# ESP32-C6_Qwiic_Micro.net
KiCad netlist of a schematic drawn in EAGLE
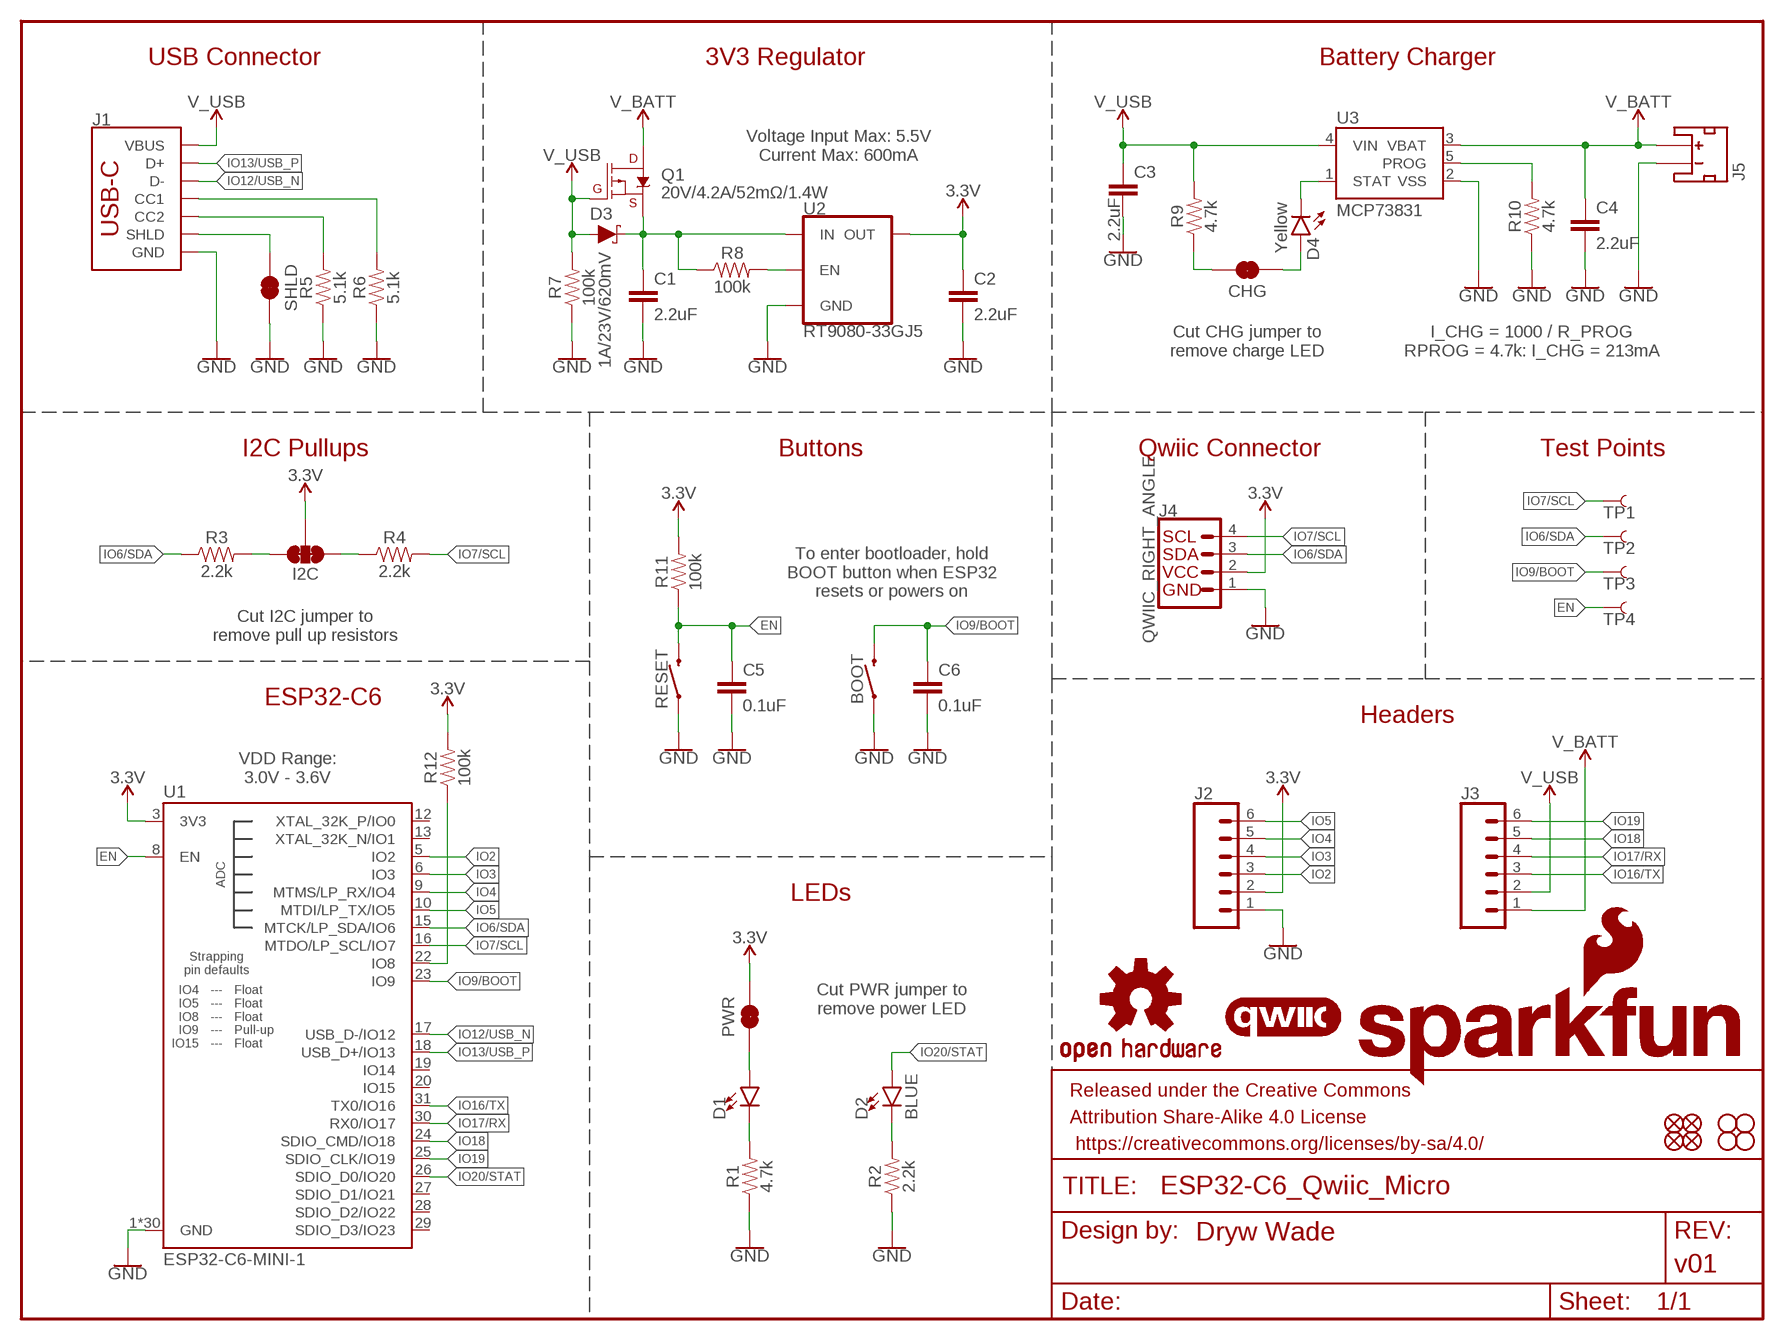
[diagram p0: schematic, sheet 1]

(export (version "E")
  (design (tool "Eeschema 10.0.6"))
  (components
    (comp (ref "BOOT")
      (value "MOMENTARY-SWITCH-SPST-SMD-4.6X2.8MM")
      (footprint "eagle-import:TACTILE_SWITCH_SMD_4.6X2.8MM")
      (libsource (lib "eagle-import") (part "MOMENTARY-SWITCH-SPST-SMD-4.6X2.8MM"))
    )
    (comp (ref "C1")
      (value "2.2uF")
      (footprint "eagle-import:0402-TIGHT")
      (libsource (lib "eagle-import") (part "2.2UF-0402_TIGHT-10V-10%-X5R"))
    )
    (comp (ref "C2")
      (value "2.2uF")
      (footprint "eagle-import:0402-TIGHT")
      (libsource (lib "eagle-import") (part "2.2UF-0402_TIGHT-10V-10%-X5R"))
    )
    (comp (ref "C3")
      (value "2.2uF")
      (footprint "eagle-import:0402-TIGHT")
      (libsource (lib "eagle-import") (part "2.2UF-0402_TIGHT-10V-10%-X5R"))
    )
    (comp (ref "C4")
      (value "2.2uF")
      (footprint "eagle-import:0402-TIGHT")
      (libsource (lib "eagle-import") (part "2.2UF-0402_TIGHT-10V-10%-X5R"))
    )
    (comp (ref "C5")
      (value "0.1uF")
      (footprint "eagle-import:0402-TIGHT")
      (libsource (lib "eagle-import") (part "0.1UF-0402T-6.3V-10%-X7R"))
    )
    (comp (ref "C6")
      (value "0.1uF")
      (footprint "eagle-import:0402-TIGHT")
      (libsource (lib "eagle-import") (part "0.1UF-0402T-6.3V-10%-X7R"))
    )
    (comp (ref "CHG")
      (value "JUMPER-SMT_2_NC_TRACE_SILK")
      (footprint "eagle-import:SMT-JUMPER_2_NC_TRACE_SILK")
      (libsource (lib "eagle-import") (part "JUMPER-SMT_2_NC_TRACE_SILK"))
    )
    (comp (ref "D1")
      (value "LED-RED_0603-KB")
      (footprint "eagle-import:LED-0603")
      (libsource (lib "eagle-import") (part "LED-RED_0603-KB"))
    )
    (comp (ref "D2")
      (value "BLUE")
      (footprint "eagle-import:LED-0603")
      (libsource (lib "eagle-import") (part "LED-BLUE0603"))
    )
    (comp (ref "D3")
      (value "1A/23V/620mV")
      (footprint "eagle-import:SOD-323")
      (libsource (lib "eagle-import") (part "DIODE-SCHOTTKY-BAT20J"))
    )
    (comp (ref "D4")
      (value "Yellow")
      (footprint "eagle-import:LED-0603")
      (libsource (lib "eagle-import") (part "LED-YELLOW0603"))
    )
    (comp (ref "FD1")
      (value "FIDUCIALUFIDUCIAL")
      (footprint "eagle-import:FIDUCIAL-MICRO")
      (libsource (lib "eagle-import") (part "FIDUCIALUFIDUCIAL"))
    )
    (comp (ref "FD2")
      (value "FIDUCIALUFIDUCIAL")
      (footprint "eagle-import:FIDUCIAL-MICRO")
      (libsource (lib "eagle-import") (part "FIDUCIALUFIDUCIAL"))
    )
    (comp (ref "FD3")
      (value "FIDUCIALUFIDUCIAL")
      (footprint "eagle-import:FIDUCIAL-MICRO")
      (libsource (lib "eagle-import") (part "FIDUCIALUFIDUCIAL"))
    )
    (comp (ref "FD4")
      (value "FIDUCIALUFIDUCIAL")
      (footprint "eagle-import:FIDUCIAL-MICRO")
      (libsource (lib "eagle-import") (part "FIDUCIALUFIDUCIAL"))
    )
    (comp (ref "FRAME1")
      (value "FRAME-LETTER")
      (footprint "eagle-import:CREATIVE_COMMONS")
      (fields (field (name "DESIGNER") "Dryw Wade") (field (name "REV") "v01"))
      (libsource (lib "eagle-import") (part "FRAME-LETTER"))
    )
    (comp (ref "H1")
      (value "STAND-OFF")
      (footprint "eagle-import:STAND-OFF")
      (libsource (lib "eagle-import") (part "STAND-OFF"))
    )
    (comp (ref "H2")
      (value "STAND-OFF")
      (footprint "eagle-import:STAND-OFF")
      (libsource (lib "eagle-import") (part "STAND-OFF"))
    )
    (comp (ref "H3")
      (value "STAND-OFF")
      (footprint "eagle-import:STAND-OFF")
      (libsource (lib "eagle-import") (part "STAND-OFF"))
    )
    (comp (ref "H4")
      (value "STAND-OFF")
      (footprint "eagle-import:STAND-OFF")
      (libsource (lib "eagle-import") (part "STAND-OFF"))
    )
    (comp (ref "I2C")
      (value "JUMPER-SMT_3_2-NC_TRACE_SILK")
      (footprint "eagle-import:SMT-JUMPER_3_2-NC_TRACE_SILK")
      (libsource (lib "eagle-import") (part "JUMPER-SMT_3_2-NC_TRACE_SILK"))
    )
    (comp (ref "J1")
      (value "USB Female Type C Connector")
      (footprint "eagle-import:USB-C-16P_4LAYER-PADS")
      (libsource (lib "eagle-import") (part "USB_C_4-LAYER_PADS"))
    )
    (comp (ref "J2")
      (value "CONN_06NO_SILK_NO_POP")
      (footprint "eagle-import:1X06_NO_SILK")
      (libsource (lib "eagle-import") (part "CONN_06NO_SILK_NO_POP"))
    )
    (comp (ref "J3")
      (value "CONN_06NO_SILK_NO_POP")
      (footprint "eagle-import:1X06_NO_SILK")
      (libsource (lib "eagle-import") (part "CONN_06NO_SILK_NO_POP"))
    )
    (comp (ref "J4")
      (value "QWIIC_RIGHT_ANGLE")
      (footprint "eagle-import:JST04_1MM_RA")
      (libsource (lib "eagle-import") (part "QWIIC_CONNECTORJS-1MM"))
    )
    (comp (ref "J5")
      (value "JST_2MM_MALE")
      (footprint "eagle-import:JST-2-SMD")
      (libsource (lib "eagle-import") (part "JST_2MM_MALE"))
    )
    (comp (ref "LOGO1")
      (value "SFE_LOGO_NAME_FLAMEBLANK")
      (footprint "eagle-import:BLANK")
      (libsource (lib "eagle-import") (part "SFE_LOGO_NAME_FLAMEBLANK"))
    )
    (comp (ref "LOGO2")
      (value "OSHW-LOGOS")
      (footprint "eagle-import:OSHW-LOGO-S")
      (libsource (lib "eagle-import") (part "OSHW-LOGOS"))
    )
    (comp (ref "LOGO3")
      (value "QWIIC_LOGO_3MM")
      (footprint "eagle-import:QWIIC_3MM")
      (libsource (lib "eagle-import") (part "QWIIC_LOGO_3MM"))
    )
    (comp (ref "PWR")
      (value "JUMPER-SMT_2_NC_TRACE_SILK")
      (footprint "eagle-import:SMT-JUMPER_2_NC_TRACE_SILK")
      (libsource (lib "eagle-import") (part "JUMPER-SMT_2_NC_TRACE_SILK"))
    )
    (comp (ref "Q1")
      (value "20V/4.2A/52mΩ/1.4W")
      (footprint "eagle-import:SOT23-3")
      (libsource (lib "eagle-import") (part "MOSFET_PCH-DMG2305UX-7"))
    )
    (comp (ref "R1")
      (value "4.7k")
      (footprint "eagle-import:0402-TIGHT")
      (libsource (lib "eagle-import") (part "4.7KOHM-0402T-1/16W-1%"))
    )
    (comp (ref "R2")
      (value "2.2k")
      (footprint "eagle-import:0402-TIGHT")
      (libsource (lib "eagle-import") (part "2.2KOHM-0402T-1/16W-1%"))
    )
    (comp (ref "R3")
      (value "2.2k")
      (footprint "eagle-import:0402-TIGHT")
      (libsource (lib "eagle-import") (part "2.2KOHM-0402T-1/16W-1%"))
    )
    (comp (ref "R4")
      (value "2.2k")
      (footprint "eagle-import:0402-TIGHT")
      (libsource (lib "eagle-import") (part "2.2KOHM-0402T-1/16W-1%"))
    )
    (comp (ref "R5")
      (value "5.1k")
      (footprint "eagle-import:0402-TIGHT")
      (libsource (lib "eagle-import") (part "5.1KOHM-0402T-1/16W-1%"))
    )
    (comp (ref "R6")
      (value "5.1k")
      (footprint "eagle-import:0402-TIGHT")
      (libsource (lib "eagle-import") (part "5.1KOHM-0402T-1/16W-1%"))
    )
    (comp (ref "R7")
      (value "100k")
      (footprint "eagle-import:0402-TIGHT")
      (libsource (lib "eagle-import") (part "100KOHM-0402T-1/16W-1%"))
    )
    (comp (ref "R8")
      (value "100k")
      (footprint "eagle-import:0402-TIGHT")
      (libsource (lib "eagle-import") (part "100KOHM-0402T-1/16W-1%"))
    )
    (comp (ref "R9")
      (value "4.7k")
      (footprint "eagle-import:0402-TIGHT")
      (libsource (lib "eagle-import") (part "4.7KOHM-0402T-1/16W-1%"))
    )
    (comp (ref "R10")
      (value "4.7k")
      (footprint "eagle-import:0402-TIGHT")
      (libsource (lib "eagle-import") (part "4.7KOHM-0402T-1/16W-1%"))
    )
    (comp (ref "R11")
      (value "100k")
      (footprint "eagle-import:0402-TIGHT")
      (libsource (lib "eagle-import") (part "100KOHM-0402T-1/16W-1%"))
    )
    (comp (ref "R12")
      (value "100k")
      (footprint "eagle-import:0402-TIGHT")
      (libsource (lib "eagle-import") (part "100KOHM-0402T-1/16W-1%"))
    )
    (comp (ref "RESET")
      (value "MOMENTARY-SWITCH-SPST-SMD-4.6X2.8MM")
      (footprint "eagle-import:TACTILE_SWITCH_SMD_4.6X2.8MM")
      (libsource (lib "eagle-import") (part "MOMENTARY-SWITCH-SPST-SMD-4.6X2.8MM"))
    )
    (comp (ref "SHLD")
      (value "JUMPER-SMT_2_NC_TRACE_SILK")
      (footprint "eagle-import:SMT-JUMPER_2_NC_TRACE_SILK")
      (libsource (lib "eagle-import") (part "JUMPER-SMT_2_NC_TRACE_SILK"))
    )
    (comp (ref "TP1")
      (value "TEST-POINT3")
      (footprint "eagle-import:PAD.03X.03")
      (libsource (lib "eagle-import") (part "TEST-POINT3"))
    )
    (comp (ref "TP2")
      (value "TEST-POINT3")
      (footprint "eagle-import:PAD.03X.03")
      (libsource (lib "eagle-import") (part "TEST-POINT3"))
    )
    (comp (ref "TP3")
      (value "TEST-POINT3")
      (footprint "eagle-import:PAD.03X.03")
      (libsource (lib "eagle-import") (part "TEST-POINT3"))
    )
    (comp (ref "TP4")
      (value "TEST-POINT3")
      (footprint "eagle-import:PAD.03X.03")
      (libsource (lib "eagle-import") (part "TEST-POINT3"))
    )
    (comp (ref "U1")
      (value "ESP32-C6-MINI-1")
      (footprint "eagle-import:ESP32-C6-MINI-1")
      (libsource (lib "eagle-import") (part "ESP32-C6-MINI-1"))
    )
    (comp (ref "U2")
      (value "RT9080-33GJ5")
      (footprint "eagle-import:SOT23-5")
      (libsource (lib "eagle-import") (part "V_REG_RT9080"))
    )
    (comp (ref "U3")
      (value "MCP73831")
      (footprint "eagle-import:SOT23-5")
      (libsource (lib "eagle-import") (part "MCP73831"))
    )
  )
  (nets
    (net (code "1") (name "3.3V") (class "Default")
      (node (ref "C2") (pin "1") (pinfunction "1_1") (pintype "passive"))
      (node (ref "I2C") (pin "2") (pinfunction "2_2") (pintype "passive"))
      (node (ref "J2") (pin "2") (pinfunction "2_2") (pintype "passive"))
      (node (ref "J4") (pin "2") (pinfunction "2_2") (pintype "power_in"))
      (node (ref "PWR") (pin "2") (pinfunction "2_2") (pintype "passive"))
      (node (ref "R11") (pin "2") (pinfunction "2_2") (pintype "passive"))
      (node (ref "R12") (pin "2") (pinfunction "2_2") (pintype "passive"))
      (node (ref "U1") (pin "3") (pinfunction "3V3_3") (pintype "bidirectional"))
      (node (ref "U2") (pin "5") (pinfunction "OUT_5") (pintype "passive"))
    )
    (net (code "2") (name "EN") (class "Default")
      (node (ref "C5") (pin "1") (pinfunction "1_1") (pintype "passive"))
      (node (ref "R11") (pin "1") (pinfunction "1_1") (pintype "passive"))
      (node (ref "RESET") (pin "3") (pinfunction "2_3") (pintype "passive"))
      (node (ref "RESET") (pin "4") (pinfunction "2_4") (pintype "passive"))
      (node (ref "TP4") (pin "1") (pinfunction "1_1") (pintype "bidirectional"))
      (node (ref "U1") (pin "8") (pinfunction "EN_8") (pintype "bidirectional"))
    )
    (net (code "3") (name "GND") (class "Default")
      (node (ref "BOOT") (pin "1") (pinfunction "1_1") (pintype "passive"))
      (node (ref "BOOT") (pin "2") (pinfunction "1_2") (pintype "passive"))
      (node (ref "C1") (pin "2") (pinfunction "2_2") (pintype "passive"))
      (node (ref "C2") (pin "2") (pinfunction "2_2") (pintype "passive"))
      (node (ref "C3") (pin "2") (pinfunction "2_2") (pintype "passive"))
      (node (ref "C4") (pin "2") (pinfunction "2_2") (pintype "passive"))
      (node (ref "C5") (pin "2") (pinfunction "2_2") (pintype "passive"))
      (node (ref "C6") (pin "2") (pinfunction "2_2") (pintype "passive"))
      (node (ref "J1") (pin "GND") (pinfunction "GND_GND") (pintype "bidirectional"))
      (node (ref "J1") (pin "GND2") (pinfunction "GND_GND2") (pintype "bidirectional"))
      (node (ref "J2") (pin "1") (pinfunction "1_1") (pintype "passive"))
      (node (ref "J4") (pin "1") (pinfunction "1_1") (pintype "power_in"))
      (node (ref "J5") (pin "1") (pinfunction "-_1") (pintype "bidirectional"))
      (node (ref "R1") (pin "1") (pinfunction "1_1") (pintype "passive"))
      (node (ref "R10") (pin "1") (pinfunction "1_1") (pintype "passive"))
      (node (ref "R2") (pin "1") (pinfunction "1_1") (pintype "passive"))
      (node (ref "R5") (pin "1") (pinfunction "1_1") (pintype "passive"))
      (node (ref "R6") (pin "1") (pinfunction "1_1") (pintype "passive"))
      (node (ref "R7") (pin "1") (pinfunction "1_1") (pintype "passive"))
      (node (ref "RESET") (pin "1") (pinfunction "1_1") (pintype "passive"))
      (node (ref "RESET") (pin "2") (pinfunction "1_2") (pintype "passive"))
      (node (ref "SHLD") (pin "2") (pinfunction "2_2") (pintype "passive"))
      (node (ref "U1") (pin "1") (pinfunction "GND_1") (pintype "bidirectional"))
      (node (ref "U1") (pin "11") (pinfunction "GND_11") (pintype "bidirectional"))
      (node (ref "U1") (pin "14") (pinfunction "GND_14") (pintype "bidirectional"))
      (node (ref "U1") (pin "2") (pinfunction "GND_2") (pintype "bidirectional"))
      (node (ref "U1") (pin "36") (pinfunction "GND_36") (pintype "bidirectional"))
      (node (ref "U1") (pin "37") (pinfunction "GND_37") (pintype "bidirectional"))
      (node (ref "U1") (pin "38") (pinfunction "GND_38") (pintype "bidirectional"))
      (node (ref "U1") (pin "39") (pinfunction "GND_39") (pintype "bidirectional"))
      (node (ref "U1") (pin "40") (pinfunction "GND_40") (pintype "bidirectional"))
      (node (ref "U1") (pin "41") (pinfunction "GND_41") (pintype "bidirectional"))
      (node (ref "U1") (pin "42") (pinfunction "GND_42") (pintype "bidirectional"))
      (node (ref "U1") (pin "43") (pinfunction "GND_43") (pintype "bidirectional"))
      (node (ref "U1") (pin "44") (pinfunction "GND_44") (pintype "bidirectional"))
      (node (ref "U1") (pin "45") (pinfunction "GND_45") (pintype "bidirectional"))
      (node (ref "U1") (pin "46") (pinfunction "GND_46") (pintype "bidirectional"))
      (node (ref "U1") (pin "47") (pinfunction "GND_47") (pintype "bidirectional"))
      (node (ref "U1") (pin "48") (pinfunction "GND_48") (pintype "bidirectional"))
      (node (ref "U1") (pin "49.1") (pinfunction "GND_49.1") (pintype "bidirectional"))
      (node (ref "U1") (pin "49.2") (pinfunction "GND_49.2") (pintype "bidirectional"))
      (node (ref "U1") (pin "49.3") (pinfunction "GND_49.3") (pintype "bidirectional"))
      (node (ref "U1") (pin "49.4") (pinfunction "GND_49.4") (pintype "bidirectional"))
      (node (ref "U1") (pin "49.5") (pinfunction "GND_49.5") (pintype "bidirectional"))
      (node (ref "U1") (pin "49.6") (pinfunction "GND_49.6") (pintype "bidirectional"))
      (node (ref "U1") (pin "49.7") (pinfunction "GND_49.7") (pintype "bidirectional"))
      (node (ref "U1") (pin "49.8") (pinfunction "GND_49.8") (pintype "bidirectional"))
      (node (ref "U1") (pin "49.9") (pinfunction "GND_49.9") (pintype "bidirectional"))
      (node (ref "U1") (pin "50") (pinfunction "GND_50") (pintype "bidirectional"))
      (node (ref "U1") (pin "51") (pinfunction "GND_51") (pintype "bidirectional"))
      (node (ref "U1") (pin "52") (pinfunction "GND_52") (pintype "bidirectional"))
      (node (ref "U1") (pin "53") (pinfunction "GND_53") (pintype "bidirectional"))
      (node (ref "U2") (pin "2") (pinfunction "GND_2") (pintype "input"))
      (node (ref "U3") (pin "2") (pinfunction "VSS_2") (pintype "power_in"))
    )
    (net (code "4") (name "IO2") (class "Default")
      (node (ref "J2") (pin "3") (pinfunction "3_3") (pintype "passive"))
      (node (ref "U1") (pin "5") (pinfunction "IO2_5") (pintype "bidirectional"))
    )
    (net (code "5") (name "IO3") (class "Default")
      (node (ref "J2") (pin "4") (pinfunction "4_4") (pintype "passive"))
      (node (ref "U1") (pin "6") (pinfunction "IO3_6") (pintype "bidirectional"))
    )
    (net (code "6") (name "IO4") (class "Default")
      (node (ref "J2") (pin "5") (pinfunction "5_5") (pintype "passive"))
      (node (ref "U1") (pin "9") (pinfunction "MTMS/LP_RX/IO4_9") (pintype "bidirectional"))
    )
    (net (code "7") (name "IO5") (class "Default")
      (node (ref "J2") (pin "6") (pinfunction "6_6") (pintype "passive"))
      (node (ref "U1") (pin "10") (pinfunction "MTDI/LP_TX/IO5_10") (pintype "bidirectional"))
    )
    (net (code "8") (name "IO6{slash}SDA") (class "Default")
      (node (ref "J4") (pin "3") (pinfunction "3_3") (pintype "passive"))
      (node (ref "R3") (pin "1") (pinfunction "1_1") (pintype "passive"))
      (node (ref "TP2") (pin "1") (pinfunction "1_1") (pintype "bidirectional"))
      (node (ref "U1") (pin "15") (pinfunction "MTCK/LP_SDA/IO6_15") (pintype "bidirectional"))
    )
    (net (code "9") (name "IO7{slash}SCL") (class "Default")
      (node (ref "J4") (pin "4") (pinfunction "4_4") (pintype "passive"))
      (node (ref "R4") (pin "2") (pinfunction "2_2") (pintype "passive"))
      (node (ref "TP1") (pin "1") (pinfunction "1_1") (pintype "bidirectional"))
      (node (ref "U1") (pin "16") (pinfunction "MTDO/LP_SCL/IO7_16") (pintype "bidirectional"))
    )
    (net (code "10") (name "IO9{slash}BOOT") (class "Default")
      (node (ref "BOOT") (pin "3") (pinfunction "2_3") (pintype "passive"))
      (node (ref "BOOT") (pin "4") (pinfunction "2_4") (pintype "passive"))
      (node (ref "C6") (pin "1") (pinfunction "1_1") (pintype "passive"))
      (node (ref "TP3") (pin "1") (pinfunction "1_1") (pintype "bidirectional"))
      (node (ref "U1") (pin "23") (pinfunction "IO9_23") (pintype "bidirectional"))
    )
    (net (code "11") (name "IO12{slash}USB_N") (class "Default")
      (node (ref "J1") (pin "A7") (pinfunction "D-_A7") (pintype "bidirectional"))
      (node (ref "J1") (pin "B7") (pinfunction "D-_B7") (pintype "bidirectional"))
      (node (ref "U1") (pin "17") (pinfunction "USB_D-/IO12_17") (pintype "bidirectional"))
    )
    (net (code "12") (name "IO13{slash}USB_P") (class "Default")
      (node (ref "J1") (pin "A6") (pinfunction "D+_A6") (pintype "bidirectional"))
      (node (ref "J1") (pin "B6") (pinfunction "D+_B6") (pintype "bidirectional"))
      (node (ref "U1") (pin "18") (pinfunction "USB_D+/IO13_18") (pintype "bidirectional"))
    )
    (net (code "13") (name "IO16{slash}TX") (class "Default")
      (node (ref "J3") (pin "3") (pinfunction "3_3") (pintype "passive"))
      (node (ref "U1") (pin "31") (pinfunction "TX0/IO16_31") (pintype "bidirectional"))
    )
    (net (code "14") (name "IO17{slash}RX") (class "Default")
      (node (ref "J3") (pin "4") (pinfunction "4_4") (pintype "passive"))
      (node (ref "U1") (pin "30") (pinfunction "RX0/IO17_30") (pintype "bidirectional"))
    )
    (net (code "15") (name "IO18") (class "Default")
      (node (ref "J3") (pin "5") (pinfunction "5_5") (pintype "passive"))
      (node (ref "U1") (pin "24") (pinfunction "SDIO_CMD/IO18_24") (pintype "bidirectional"))
    )
    (net (code "16") (name "IO19") (class "Default")
      (node (ref "J3") (pin "6") (pinfunction "6_6") (pintype "passive"))
      (node (ref "U1") (pin "25") (pinfunction "SDIO_CLK/IO19_25") (pintype "bidirectional"))
    )
    (net (code "17") (name "IO20{slash}STAT") (class "Default")
      (node (ref "D2") (pin "A") (pinfunction "A_A") (pintype "passive"))
      (node (ref "U1") (pin "26") (pinfunction "SDIO_D0/IO20_26") (pintype "bidirectional"))
    )
    (net (code "18") (name "Net-(CHG-Pad1)") (class "Default")
      (node (ref "CHG") (pin "1") (pinfunction "1_1") (pintype "passive"))
      (node (ref "D4") (pin "A") (pinfunction "A_A") (pintype "passive"))
    )
    (net (code "19") (name "Net-(CHG-Pad2)") (class "Default")
      (node (ref "CHG") (pin "2") (pinfunction "2_2") (pintype "passive"))
      (node (ref "R9") (pin "1") (pinfunction "1_1") (pintype "passive"))
    )
    (net (code "20") (name "Net-(D1-PadA)") (class "Default")
      (node (ref "D1") (pin "A") (pinfunction "A_A") (pintype "passive"))
      (node (ref "PWR") (pin "1") (pinfunction "1_1") (pintype "passive"))
    )
    (net (code "21") (name "Net-(D1-PadC)") (class "Default")
      (node (ref "D1") (pin "C") (pinfunction "C_C") (pintype "passive"))
      (node (ref "R1") (pin "2") (pinfunction "2_2") (pintype "passive"))
    )
    (net (code "22") (name "Net-(D2-PadC)") (class "Default")
      (node (ref "D2") (pin "C") (pinfunction "C_C") (pintype "passive"))
      (node (ref "R2") (pin "2") (pinfunction "2_2") (pintype "passive"))
    )
    (net (code "23") (name "Net-(I2C-Pad1)") (class "Default")
      (node (ref "I2C") (pin "1") (pinfunction "1_1") (pintype "passive"))
      (node (ref "R4") (pin "1") (pinfunction "1_1") (pintype "passive"))
    )
    (net (code "24") (name "Net-(I2C-Pad3)") (class "Default")
      (node (ref "I2C") (pin "3") (pinfunction "3_3") (pintype "passive"))
      (node (ref "R3") (pin "2") (pinfunction "2_2") (pintype "passive"))
    )
    (net (code "25") (name "Net-(J1-CC1)") (class "Default")
      (node (ref "J1") (pin "A5") (pinfunction "CC1_A5") (pintype "bidirectional"))
      (node (ref "R6") (pin "2") (pinfunction "2_2") (pintype "passive"))
    )
    (net (code "26") (name "Net-(J1-CC2)") (class "Default")
      (node (ref "J1") (pin "B5") (pinfunction "CC2_B5") (pintype "bidirectional"))
      (node (ref "R5") (pin "2") (pinfunction "2_2") (pintype "passive"))
    )
    (net (code "27") (name "Net-(J1-SHLD-PadSHLD1)") (class "Default")
      (node (ref "J1") (pin "SHLD1") (pinfunction "SHLD_SHLD1") (pintype "bidirectional"))
      (node (ref "J1") (pin "SHLD2") (pinfunction "SHLD_SHLD2") (pintype "bidirectional"))
      (node (ref "J1") (pin "SHLD3") (pinfunction "SHLD_SHLD3") (pintype "bidirectional"))
      (node (ref "J1") (pin "SHLD4") (pinfunction "SHLD_SHLD4") (pintype "bidirectional"))
      (node (ref "SHLD") (pin "1") (pinfunction "1_1") (pintype "passive"))
    )
    (net (code "28") (name "Net-(Q1-S)") (class "Default")
      (node (ref "C1") (pin "1") (pinfunction "1_1") (pintype "passive"))
      (node (ref "D3") (pin "C") (pinfunction "C_C") (pintype "passive"))
      (node (ref "Q1") (pin "2") (pinfunction "S_2") (pintype "bidirectional"))
      (node (ref "R8") (pin "1") (pinfunction "1_1") (pintype "passive"))
      (node (ref "U2") (pin "1") (pinfunction "IN_1") (pintype "input"))
    )
    (net (code "29") (name "Net-(U1-IO8)") (class "Default")
      (node (ref "R12") (pin "1") (pinfunction "1_1") (pintype "passive"))
      (node (ref "U1") (pin "22") (pinfunction "IO8_22") (pintype "bidirectional"))
    )
    (net (code "30") (name "Net-(U2-EN)") (class "Default")
      (node (ref "R8") (pin "2") (pinfunction "2_2") (pintype "passive"))
      (node (ref "U2") (pin "3") (pinfunction "EN_3") (pintype "input"))
    )
    (net (code "31") (name "Net-(U3-PROG)") (class "Default")
      (node (ref "R10") (pin "2") (pinfunction "2_2") (pintype "passive"))
      (node (ref "U3") (pin "5") (pinfunction "PROG_5") (pintype "input"))
    )
    (net (code "32") (name "Net-(U3-STAT)") (class "Default")
      (node (ref "D4") (pin "C") (pinfunction "C_C") (pintype "passive"))
      (node (ref "U3") (pin "1") (pinfunction "STAT_1") (pintype "output"))
    )
    (net (code "33") (name "V_BATT") (class "Default")
      (node (ref "C4") (pin "1") (pinfunction "1_1") (pintype "passive"))
      (node (ref "J3") (pin "1") (pinfunction "1_1") (pintype "passive"))
      (node (ref "J5") (pin "2") (pinfunction "+_2") (pintype "bidirectional"))
      (node (ref "Q1") (pin "3") (pinfunction "D_3") (pintype "bidirectional"))
      (node (ref "U3") (pin "3") (pinfunction "VBAT_3") (pintype "power_in"))
    )
    (net (code "34") (name "V_USB") (class "Default")
      (node (ref "C3") (pin "1") (pinfunction "1_1") (pintype "passive"))
      (node (ref "D3") (pin "A") (pinfunction "A_A") (pintype "passive"))
      (node (ref "J1") (pin "VBUS1") (pinfunction "VBUS_VBUS1") (pintype "bidirectional"))
      (node (ref "J1") (pin "VBUS2") (pinfunction "VBUS_VBUS2") (pintype "bidirectional"))
      (node (ref "J3") (pin "2") (pinfunction "2_2") (pintype "passive"))
      (node (ref "Q1") (pin "1") (pinfunction "G_1") (pintype "bidirectional"))
      (node (ref "R7") (pin "2") (pinfunction "2_2") (pintype "passive"))
      (node (ref "R9") (pin "2") (pinfunction "2_2") (pintype "passive"))
      (node (ref "U3") (pin "4") (pinfunction "VIN_4") (pintype "power_in"))
    )
    (net (code "35") (name "unconnected-(J5-PAD1-PadNC1)") (class "Default")
      (node (ref "J5") (pin "NC1") (pinfunction "PAD1_NC1") (pintype "bidirectional"))
    )
    (net (code "36") (name "unconnected-(J5-PAD2-PadNC2)") (class "Default")
      (node (ref "J5") (pin "NC2") (pinfunction "PAD2_NC2") (pintype "bidirectional"))
    )
    (net (code "37") (name "unconnected-(U1-IO14-Pad19)") (class "Default")
      (node (ref "U1") (pin "19") (pinfunction "IO14_19") (pintype "bidirectional"))
    )
    (net (code "38") (name "unconnected-(U1-IO15-Pad20)") (class "Default")
      (node (ref "U1") (pin "20") (pinfunction "IO15_20") (pintype "bidirectional"))
    )
    (net (code "39") (name "unconnected-(U1-SDIO_D1{slash}IO21-Pad27)") (class "Default")
      (node (ref "U1") (pin "27") (pinfunction "SDIO_D1/IO21_27") (pintype "bidirectional"))
    )
    (net (code "40") (name "unconnected-(U1-SDIO_D2{slash}IO22-Pad28)") (class "Default")
      (node (ref "U1") (pin "28") (pinfunction "SDIO_D2/IO22_28") (pintype "bidirectional"))
    )
    (net (code "41") (name "unconnected-(U1-SDIO_D3{slash}IO23-Pad29)") (class "Default")
      (node (ref "U1") (pin "29") (pinfunction "SDIO_D3/IO23_29") (pintype "bidirectional"))
    )
    (net (code "42") (name "unconnected-(U1-XTAL_32K_N{slash}IO1-Pad13)") (class "Default")
      (node (ref "U1") (pin "13") (pinfunction "XTAL_32K_N/IO1_13") (pintype "bidirectional"))
    )
    (net (code "43") (name "unconnected-(U1-XTAL_32K_P{slash}IO0-Pad12)") (class "Default")
      (node (ref "U1") (pin "12") (pinfunction "XTAL_32K_P/IO0_12") (pintype "bidirectional"))
    )
  )
)
